# atmelModule.net
KiCad netlist of a schematic drawn in EAGLE
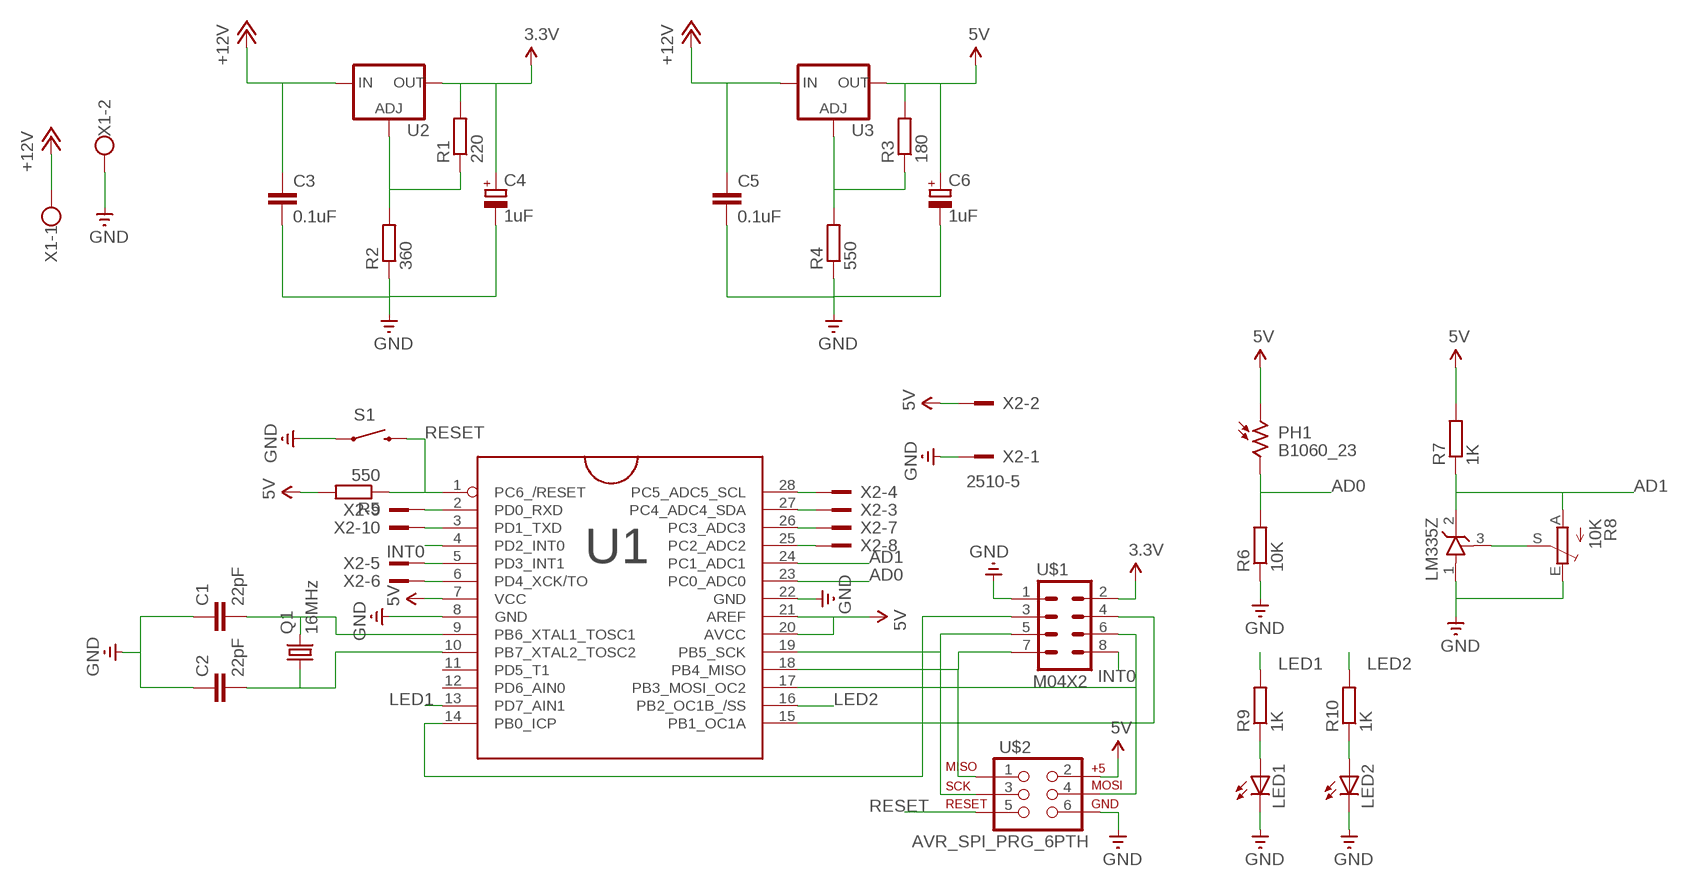
[diagram p0: schematic, sheet 1]

(export (version "E")
  (design (tool "Eeschema 10.0.6"))
  (components
    (comp (ref "C1")
      (value "22pF")
      (footprint "eagle-import:CAP-PTH-SMALL2")
      (libsource (lib "eagle-import") (part "CAPPTH2"))
    )
    (comp (ref "C2")
      (value "22pF")
      (footprint "eagle-import:CAP-PTH-SMALL2")
      (libsource (lib "eagle-import") (part "CAPPTH2"))
    )
    (comp (ref "C3")
      (value "0.1uF")
      (footprint "eagle-import:CAP-PTH-SMALL2")
      (libsource (lib "eagle-import") (part "CAPPTH2"))
    )
    (comp (ref "C4")
      (value "1uF")
      (footprint "eagle-import:E1,8-4")
      (libsource (lib "eagle-import") (part "CPOL-EUE1.8-4"))
    )
    (comp (ref "C5")
      (value "0.1uF")
      (footprint "eagle-import:CAP-PTH-SMALL2")
      (libsource (lib "eagle-import") (part "CAPPTH2"))
    )
    (comp (ref "C6")
      (value "1uF")
      (footprint "eagle-import:E1,8-4")
      (libsource (lib "eagle-import") (part "CPOL-EUE1.8-4"))
    )
    (comp (ref "IC1")
      (value "LT1009CZ")
      (footprint "eagle-import:TO92")
      (libsource (lib "eagle-import") (part "LT1009ZC"))
    )
    (comp (ref "LED1")
      (value "LED5MM")
      (footprint "eagle-import:LED5MM")
      (libsource (lib "eagle-import") (part "LED5MM"))
    )
    (comp (ref "LED2")
      (value "LED5MM")
      (footprint "eagle-import:LED5MM")
      (libsource (lib "eagle-import") (part "LED5MM"))
    )
    (comp (ref "PH1")
      (value "B1060_23")
      (footprint "eagle-import:TO-8_B10")
      (libsource (lib "eagle-import") (part "?1060B_23"))
    )
    (comp (ref "Q1")
      (value "16MHz")
      (footprint "eagle-import:HC49U-V")
      (libsource (lib "eagle-import") (part "CRYTALHC49U-V"))
    )
    (comp (ref "R1")
      (value "220")
      (footprint "eagle-import:0207_7")
      (libsource (lib "eagle-import") (part "R-EU_0207/7"))
    )
    (comp (ref "R2")
      (value "360")
      (footprint "eagle-import:0207_7")
      (libsource (lib "eagle-import") (part "R-EU_0207/7"))
    )
    (comp (ref "R3")
      (value "180")
      (footprint "eagle-import:0207_7")
      (libsource (lib "eagle-import") (part "R-EU_0207/7"))
    )
    (comp (ref "R4")
      (value "550")
      (footprint "eagle-import:0207_7")
      (libsource (lib "eagle-import") (part "R-EU_0207/7"))
    )
    (comp (ref "R5")
      (value "550")
      (footprint "eagle-import:0207_7")
      (libsource (lib "eagle-import") (part "R-EU_0207/7"))
    )
    (comp (ref "R6")
      (value "10K")
      (footprint "eagle-import:0207_7")
      (libsource (lib "eagle-import") (part "R-EU_0207/7"))
    )
    (comp (ref "R7")
      (value "1K")
      (footprint "eagle-import:0207_7")
      (libsource (lib "eagle-import") (part "R-EU_0207/7"))
    )
    (comp (ref "R8")
      (value "10K")
      (footprint "eagle-import:RJ9W")
      (libsource (lib "eagle-import") (part "TRIM_EU-RJ9W"))
    )
    (comp (ref "R9")
      (value "1K")
      (footprint "eagle-import:0207_7")
      (libsource (lib "eagle-import") (part "R-EU_0207/7"))
    )
    (comp (ref "R10")
      (value "1K")
      (footprint "eagle-import:0207_7")
      (libsource (lib "eagle-import") (part "R-EU_0207/7"))
    )
    (comp (ref "S1")
      (value "SWITCH-MOMENTARY-2PTH")
      (footprint "eagle-import:TACTILE-PTH")
      (libsource (lib "eagle-import") (part "SWITCH-MOMENTARY-2PTH"))
    )
    (comp (ref "U$1")
      (value "M04X2")
      (footprint "eagle-import:2X4")
      (libsource (lib "eagle-import") (part "M04X2"))
    )
    (comp (ref "U$2")
      (value "AVR_SPI_PRG_6PTH")
      (footprint "eagle-import:2X3")
      (libsource (lib "eagle-import") (part "AVR_SPI_PRG_6PTH"))
    )
    (comp (ref "U1")
      (value "ATMEGA8_PDIP28_PDIP")
      (footprint "eagle-import:DIL-28-3")
      (libsource (lib "eagle-import") (part "ATMEGA8_PDIP28_PDIP"))
    )
    (comp (ref "U2")
      (value "V_REG_317SINK")
      (footprint "eagle-import:TO220-ADJ")
      (libsource (lib "eagle-import") (part "V_REG_317SINK"))
    )
    (comp (ref "U3")
      (value "V_REG_317SINK")
      (footprint "eagle-import:TO220-ADJ")
      (libsource (lib "eagle-import") (part "V_REG_317SINK"))
    )
    (comp (ref "X1")
      (value "W237-102")
      (footprint "eagle-import:W237-102")
      (fields (field (name "MPN") "237-102"))
      (libsource (lib "eagle-import") (part "W237-102"))
    )
    (comp (ref "X2")
      (value "2510-5")
      (footprint "eagle-import:PAK100_2500-5-10")
      (libsource (lib "eagle-import") (part "2510-5"))
    )
  )
  (nets
    (net (code "1") (name "+12V") (class "Default")
      (node (ref "C3") (pin "1") (pinfunction "1_1") (pintype "passive"))
      (node (ref "C5") (pin "1") (pinfunction "1_1") (pintype "passive"))
      (node (ref "U2") (pin "IN") (pinfunction "IN_IN") (pintype "input"))
      (node (ref "U3") (pin "IN") (pinfunction "IN_IN") (pintype "input"))
      (node (ref "X1") (pin "1") (pinfunction "KL_1") (pintype "passive"))
    )
    (net (code "2") (name "/AD0") (class "Default")
      (node (ref "PH1") (pin "2") (pinfunction "2_2") (pintype "passive"))
      (node (ref "R6") (pin "2") (pinfunction "2_2") (pintype "passive"))
      (node (ref "U1") (pin "23") (pinfunction "PC0_ADC0_23") (pintype "bidirectional"))
    )
    (net (code "3") (name "/AD1") (class "Default")
      (node (ref "IC1") (pin "2") (pinfunction "C_2") (pintype "passive"))
      (node (ref "R7") (pin "1") (pinfunction "1_1") (pintype "passive"))
      (node (ref "R8") (pin "A") (pinfunction "A_A") (pintype "passive"))
      (node (ref "U1") (pin "24") (pinfunction "PC1_ADC1_24") (pintype "bidirectional"))
    )
    (net (code "4") (name "/INT0") (class "Default")
      (node (ref "U$1") (pin "8") (pinfunction "8_8") (pintype "passive"))
      (node (ref "U1") (pin "4") (pinfunction "PD2_INT0_4") (pintype "bidirectional"))
    )
    (net (code "5") (name "/LED1") (class "Default")
      (node (ref "R9") (pin "2") (pinfunction "2_2") (pintype "passive"))
      (node (ref "U1") (pin "13") (pinfunction "PD7_AIN1_13") (pintype "bidirectional"))
    )
    (net (code "6") (name "/LED2") (class "Default")
      (node (ref "R10") (pin "2") (pinfunction "2_2") (pintype "passive"))
      (node (ref "U1") (pin "16") (pinfunction "PB2_OC1B_/SS_16") (pintype "bidirectional"))
    )
    (net (code "7") (name "/RESET") (class "Default")
      (node (ref "R5") (pin "1") (pinfunction "1_1") (pintype "passive"))
      (node (ref "S1") (pin "3") (pinfunction "2_3") (pintype "passive"))
      (node (ref "U$2") (pin "5") (pinfunction "5_5") (pintype "passive"))
      (node (ref "U1") (pin "1") (pinfunction "PC6_/RESET_1") (pintype "bidirectional"))
    )
    (net (code "8") (name "3.3V") (class "Default")
      (node (ref "C4") (pin "+") (pinfunction "+_+") (pintype "passive"))
      (node (ref "R1") (pin "2") (pinfunction "2_2") (pintype "passive"))
      (node (ref "U$1") (pin "2") (pinfunction "2_2") (pintype "passive"))
      (node (ref "U2") (pin "OUT") (pinfunction "OUT_OUT") (pintype "output"))
    )
    (net (code "9") (name "5V") (class "Default")
      (node (ref "C6") (pin "+") (pinfunction "+_+") (pintype "passive"))
      (node (ref "PH1") (pin "1") (pinfunction "1_1") (pintype "passive"))
      (node (ref "R3") (pin "2") (pinfunction "2_2") (pintype "passive"))
      (node (ref "R5") (pin "2") (pinfunction "2_2") (pintype "passive"))
      (node (ref "R7") (pin "2") (pinfunction "2_2") (pintype "passive"))
      (node (ref "U$2") (pin "2") (pinfunction "2_2") (pintype "passive"))
      (node (ref "U1") (pin "20") (pinfunction "AVCC_20") (pintype "power_in"))
      (node (ref "U1") (pin "21") (pinfunction "AREF_21") (pintype "power_in"))
      (node (ref "U1") (pin "7") (pinfunction "VCC_7") (pintype "power_in"))
      (node (ref "U3") (pin "OUT") (pinfunction "OUT_OUT") (pintype "output"))
      (node (ref "X2") (pin "2") (pinfunction "KL_2") (pintype "passive"))
    )
    (net (code "10") (name "GND") (class "Default")
      (node (ref "C1") (pin "1") (pinfunction "1_1") (pintype "passive"))
      (node (ref "C2") (pin "1") (pinfunction "1_1") (pintype "passive"))
      (node (ref "C3") (pin "2") (pinfunction "2_2") (pintype "passive"))
      (node (ref "C4") (pin "-") (pinfunction "-_-") (pintype "passive"))
      (node (ref "C5") (pin "2") (pinfunction "2_2") (pintype "passive"))
      (node (ref "C6") (pin "-") (pinfunction "-_-") (pintype "passive"))
      (node (ref "IC1") (pin "1") (pinfunction "A_1") (pintype "passive"))
      (node (ref "LED1") (pin "K") (pinfunction "C_K") (pintype "passive"))
      (node (ref "LED2") (pin "K") (pinfunction "C_K") (pintype "passive"))
      (node (ref "R2") (pin "1") (pinfunction "1_1") (pintype "passive"))
      (node (ref "R4") (pin "1") (pinfunction "1_1") (pintype "passive"))
      (node (ref "R6") (pin "1") (pinfunction "1_1") (pintype "passive"))
      (node (ref "R8") (pin "E") (pinfunction "E_E") (pintype "passive"))
      (node (ref "S1") (pin "1") (pinfunction "1_1") (pintype "passive"))
      (node (ref "U$1") (pin "1") (pinfunction "1_1") (pintype "passive"))
      (node (ref "U$2") (pin "6") (pinfunction "6_6") (pintype "passive"))
      (node (ref "U1") (pin "22") (pinfunction "GND_22") (pintype "power_in"))
      (node (ref "U1") (pin "8") (pinfunction "GND_8") (pintype "power_in"))
      (node (ref "X1") (pin "2") (pinfunction "KL_2") (pintype "passive"))
      (node (ref "X2") (pin "1") (pinfunction "KL_1") (pintype "passive"))
    )
    (net (code "11") (name "Net-(IC1-R)") (class "Default")
      (node (ref "IC1") (pin "3") (pinfunction "R_3") (pintype "passive"))
      (node (ref "R8") (pin "S") (pinfunction "S_S") (pintype "passive"))
    )
    (net (code "12") (name "Net-(LED1-PadA)") (class "Default")
      (node (ref "LED1") (pin "A") (pinfunction "A_A") (pintype "passive"))
      (node (ref "R9") (pin "1") (pinfunction "1_1") (pintype "passive"))
    )
    (net (code "13") (name "Net-(LED2-PadA)") (class "Default")
      (node (ref "LED2") (pin "A") (pinfunction "A_A") (pintype "passive"))
      (node (ref "R10") (pin "1") (pinfunction "1_1") (pintype "passive"))
    )
    (net (code "14") (name "Net-(R1-Pad1)") (class "Default")
      (node (ref "R1") (pin "1") (pinfunction "1_1") (pintype "passive"))
      (node (ref "R2") (pin "2") (pinfunction "2_2") (pintype "passive"))
      (node (ref "U2") (pin "ADJ") (pinfunction "ADJ_ADJ") (pintype "input"))
    )
    (net (code "15") (name "Net-(R3-Pad1)") (class "Default")
      (node (ref "R3") (pin "1") (pinfunction "1_1") (pintype "passive"))
      (node (ref "R4") (pin "2") (pinfunction "2_2") (pintype "passive"))
      (node (ref "U3") (pin "ADJ") (pinfunction "ADJ_ADJ") (pintype "input"))
    )
    (net (code "16") (name "Net-(U1-PB0_ICP)") (class "Default")
      (node (ref "U$1") (pin "3") (pinfunction "3_3") (pintype "passive"))
      (node (ref "U1") (pin "14") (pinfunction "PB0_ICP_14") (pintype "bidirectional"))
    )
    (net (code "17") (name "Net-(U1-PB1_OC1A)") (class "Default")
      (node (ref "U$1") (pin "4") (pinfunction "4_4") (pintype "passive"))
      (node (ref "U1") (pin "15") (pinfunction "PB1_OC1A_15") (pintype "bidirectional"))
    )
    (net (code "18") (name "Net-(U1-PB3_MOSI_OC2)") (class "Default")
      (node (ref "U$1") (pin "6") (pinfunction "6_6") (pintype "passive"))
      (node (ref "U$2") (pin "4") (pinfunction "4_4") (pintype "passive"))
      (node (ref "U1") (pin "17") (pinfunction "PB3_MOSI_OC2_17") (pintype "bidirectional"))
    )
    (net (code "19") (name "Net-(U1-PB4_MISO)") (class "Default")
      (node (ref "U$1") (pin "7") (pinfunction "7_7") (pintype "passive"))
      (node (ref "U$2") (pin "1") (pinfunction "1_1") (pintype "passive"))
      (node (ref "U1") (pin "18") (pinfunction "PB4_MISO_18") (pintype "bidirectional"))
    )
    (net (code "20") (name "Net-(U1-PB5_SCK)") (class "Default")
      (node (ref "U$1") (pin "5") (pinfunction "5_5") (pintype "passive"))
      (node (ref "U$2") (pin "3") (pinfunction "3_3") (pintype "passive"))
      (node (ref "U1") (pin "19") (pinfunction "PB5_SCK_19") (pintype "bidirectional"))
    )
    (net (code "21") (name "Net-(U1-PB6_XTAL1_TOSC1)") (class "Default")
      (node (ref "C1") (pin "2") (pinfunction "2_2") (pintype "passive"))
      (node (ref "Q1") (pin "2") (pinfunction "2_2") (pintype "passive"))
      (node (ref "U1") (pin "9") (pinfunction "PB6_XTAL1_TOSC1_9") (pintype "bidirectional"))
    )
    (net (code "22") (name "Net-(U1-PB7_XTAL2_TOSC2)") (class "Default")
      (node (ref "C2") (pin "2") (pinfunction "2_2") (pintype "passive"))
      (node (ref "Q1") (pin "1") (pinfunction "1_1") (pintype "passive"))
      (node (ref "U1") (pin "10") (pinfunction "PB7_XTAL2_TOSC2_10") (pintype "bidirectional"))
    )
    (net (code "23") (name "Net-(U1-PC2_ADC2)") (class "Default")
      (node (ref "U1") (pin "25") (pinfunction "PC2_ADC2_25") (pintype "bidirectional"))
      (node (ref "X2") (pin "8") (pinfunction "KL_8") (pintype "passive"))
    )
    (net (code "24") (name "Net-(U1-PC3_ADC3)") (class "Default")
      (node (ref "U1") (pin "26") (pinfunction "PC3_ADC3_26") (pintype "bidirectional"))
      (node (ref "X2") (pin "7") (pinfunction "KL_7") (pintype "passive"))
    )
    (net (code "25") (name "Net-(U1-PC4_ADC4_SDA)") (class "Default")
      (node (ref "U1") (pin "27") (pinfunction "PC4_ADC4_SDA_27") (pintype "bidirectional"))
      (node (ref "X2") (pin "3") (pinfunction "KL_3") (pintype "passive"))
    )
    (net (code "26") (name "Net-(U1-PC5_ADC5_SCL)") (class "Default")
      (node (ref "U1") (pin "28") (pinfunction "PC5_ADC5_SCL_28") (pintype "bidirectional"))
      (node (ref "X2") (pin "4") (pinfunction "KL_4") (pintype "passive"))
    )
    (net (code "27") (name "Net-(U1-PD0_RXD)") (class "Default")
      (node (ref "U1") (pin "2") (pinfunction "PD0_RXD_2") (pintype "bidirectional"))
      (node (ref "X2") (pin "9") (pinfunction "KL_9") (pintype "passive"))
    )
    (net (code "28") (name "Net-(U1-PD1_TXD)") (class "Default")
      (node (ref "U1") (pin "3") (pinfunction "PD1_TXD_3") (pintype "bidirectional"))
      (node (ref "X2") (pin "10") (pinfunction "KL_10") (pintype "passive"))
    )
    (net (code "29") (name "Net-(U1-PD3_INT1)") (class "Default")
      (node (ref "U1") (pin "5") (pinfunction "PD3_INT1_5") (pintype "bidirectional"))
      (node (ref "X2") (pin "5") (pinfunction "KL_5") (pintype "passive"))
    )
    (net (code "30") (name "Net-(U1-PD4_XCK{slash}TO)") (class "Default")
      (node (ref "U1") (pin "6") (pinfunction "PD4_XCK/TO_6") (pintype "bidirectional"))
      (node (ref "X2") (pin "6") (pinfunction "KL_6") (pintype "passive"))
    )
    (net (code "31") (name "unconnected-(U1-PD5_T1-Pad11)") (class "Default")
      (node (ref "U1") (pin "11") (pinfunction "PD5_T1_11") (pintype "bidirectional"))
    )
    (net (code "32") (name "unconnected-(U1-PD6_AIN0-Pad12)") (class "Default")
      (node (ref "U1") (pin "12") (pinfunction "PD6_AIN0_12") (pintype "bidirectional"))
    )
  )
)
